# SCH_Led-Chaser_2025-10-31.net
KiCad netlist of a schematic drawn in EasyEDA
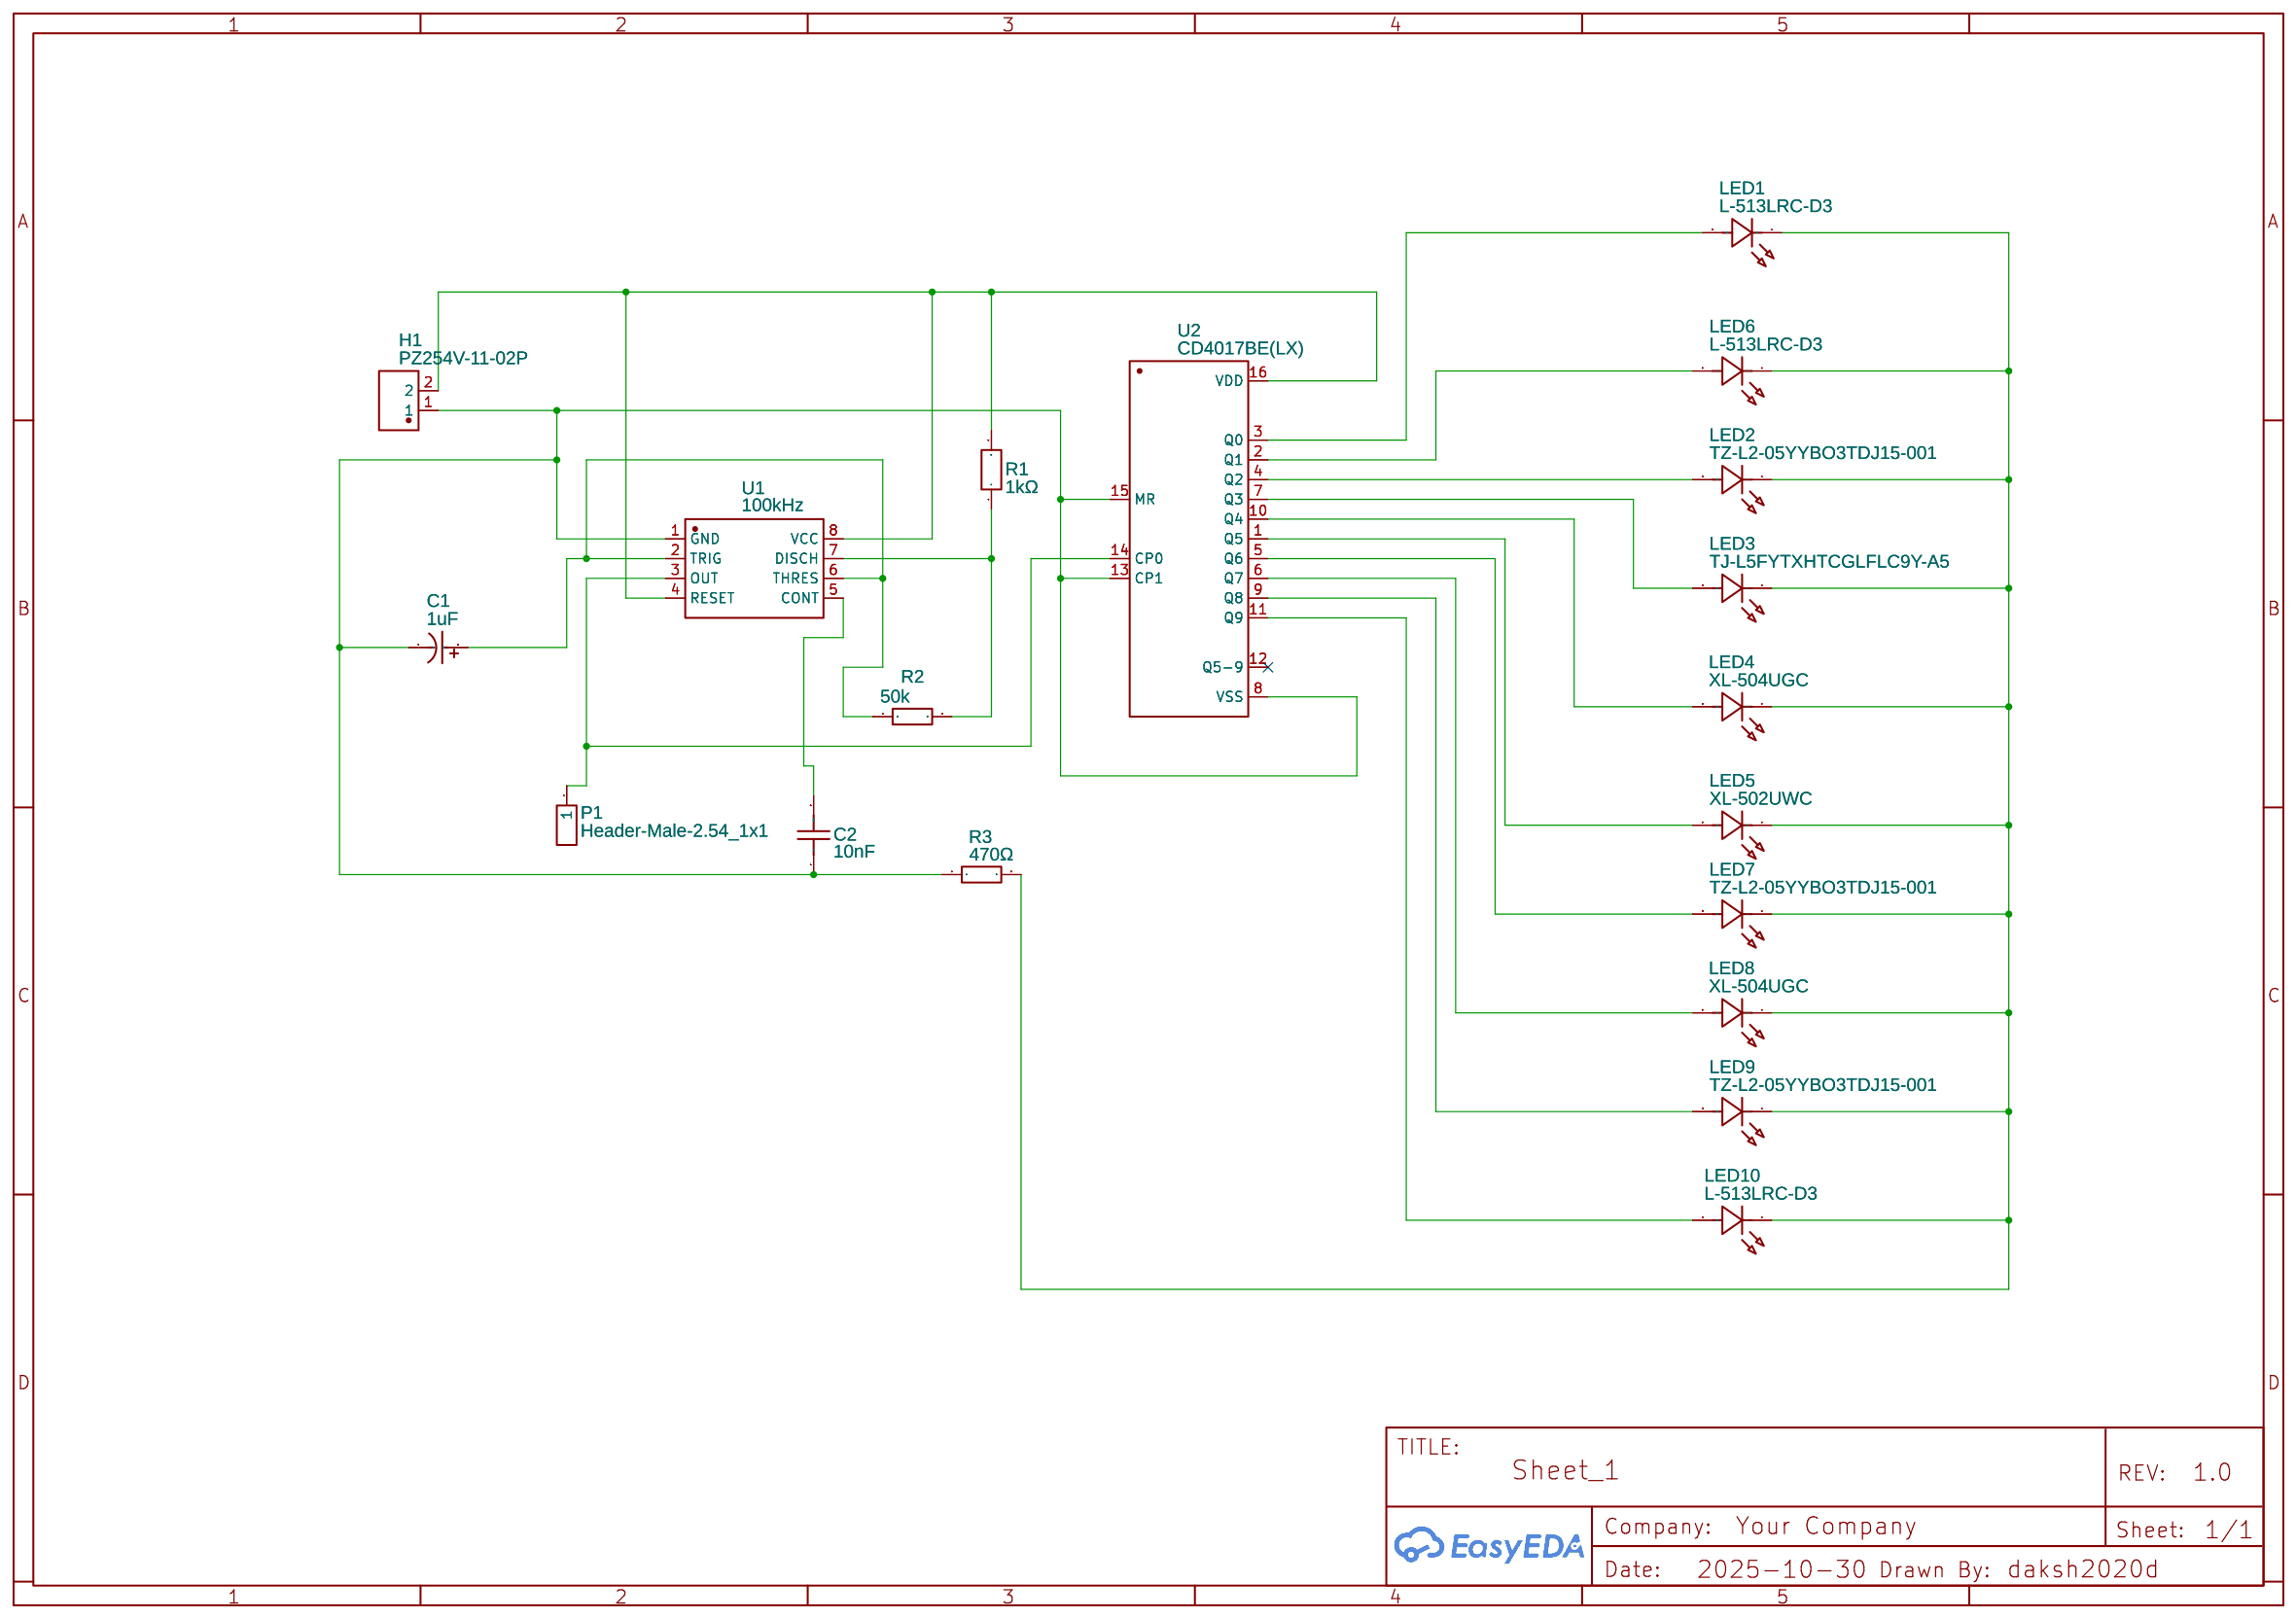
[diagram p0: schematic sheet]

(export (version "E")
  (design (tool "Eeschema 10.0.6"))
  (components
    (comp (ref "C1")
      (value "1uF")
      (fields (field (name "Manufacturer Part") "KF010M050C110A") (field (name "Manufacturer") "CapXon(丰宾)"))
      (libsource (lib "") (part "KF010M050C110A"))
    )
    (comp (ref "C2")
      (value "10nF")
      (fields (field (name "Manufacturer Part") "N09F1B103MN0B0S0N0") (field (name "Manufacturer") "STE(松田)"))
      (libsource (lib "") (part "N09F1B103MN0B0S0N0"))
    )
    (comp (ref "H1")
      (value "PZ254V-11-02P")
      (fields (field (name "Manufacturer") "XFCN(兴飞)"))
      (libsource (lib "") (part "PZ254V-11-02P"))
    )
    (comp (ref "LED1")
      (value "L-513LRC-D3")
      (fields (field (name "Manufacturer") "PARALIGHT(光鼎)"))
      (libsource (lib "") (part "L-513LRC-D3"))
    )
    (comp (ref "LED2")
      (value "TZ-L2-05YYBO3TDJ15-001")
      (fields (field (name "Manufacturer") "TUOZHAN(拓展光电)"))
      (libsource (lib "") (part "TZ-L2-05YYBO3TDJ15-001"))
    )
    (comp (ref "LED3")
      (value "TJ-L5FYTXHTCGLFLC9Y-A5")
      (fields (field (name "Manufacturer") "TOGIALED(统佳)"))
      (libsource (lib "") (part "TJ-L5FYTXHTCGLFLC9Y-A5"))
    )
    (comp (ref "LED4")
      (value "XL-504UGC")
      (fields (field (name "Manufacturer") "XINGLIGHT(成兴光)"))
      (libsource (lib "") (part "XL-504UGC"))
    )
    (comp (ref "LED5")
      (value "XL-502UWC")
      (fields (field (name "Manufacturer") "XINGLIGHT(成兴光)"))
      (libsource (lib "") (part "XL-502UWC"))
    )
    (comp (ref "LED6")
      (value "L-513LRC-D3")
      (fields (field (name "Manufacturer") "PARALIGHT(光鼎)"))
      (libsource (lib "") (part "L-513LRC-D3"))
    )
    (comp (ref "LED7")
      (value "TZ-L2-05YYBO3TDJ15-001")
      (fields (field (name "Manufacturer") "TUOZHAN(拓展光电)"))
      (libsource (lib "") (part "TZ-L2-05YYBO3TDJ15-001"))
    )
    (comp (ref "LED8")
      (value "XL-504UGC")
      (fields (field (name "Manufacturer") "XINGLIGHT(成兴光)"))
      (libsource (lib "") (part "XL-504UGC"))
    )
    (comp (ref "LED9")
      (value "TZ-L2-05YYBO3TDJ15-001")
      (fields (field (name "Manufacturer") "TUOZHAN(拓展光电)"))
      (libsource (lib "") (part "TZ-L2-05YYBO3TDJ15-001"))
    )
    (comp (ref "LED10")
      (value "L-513LRC-D3")
      (fields (field (name "Manufacturer") "PARALIGHT(光鼎)"))
      (libsource (lib "") (part "L-513LRC-D3"))
    )
    (comp (ref "P1")
      (value "Header-Male-2.54_1x1")
      (fields (field (name "Manufacturer Part") "2.54-1*1P针") (field (name "Manufacturer") "BOOMELE(博穆精密)"))
      (libsource (lib "") (part "Header-Male-2.54_1x1"))
    )
    (comp (ref "R1")
      (value "1kΩ")
      (fields (field (name "Manufacturer Part") "MF1/4W-1KΩ±1%T52") (field (name "Manufacturer") "华星机电"))
      (libsource (lib "") (part "MF1/4W-1KΩ±1%T52"))
    )
    (comp (ref "R2")
      (value "50k")
      (fields
        (field (name "Manufacturer Part") "MFR0W4F4700A50")
        (field (name "Manufacturer") "UNI-ROYAL(厚声)")
      )
      (libsource (lib "") (part "MFR0W4F4700A50"))
    )
    (comp (ref "R3")
      (value "470Ω")
      (fields
        (field (name "Manufacturer Part") "MFR0W4F4700A50")
        (field (name "Manufacturer") "UNI-ROYAL(厚声)")
      )
      (libsource (lib "") (part "MFR0W4F4700A50"))
    )
    (comp (ref "U1")
      (value "100kHz")
      (fields (field (name "Manufacturer Part") "NE555P") (field (name "Manufacturer") "TI(德州仪器)"))
      (libsource (lib "") (part "NE555P"))
    )
    (comp (ref "U2")
      (value "CD4017BE(LX)")
      (fields (field (name "Manufacturer") "LX(灵星芯微)"))
      (libsource (lib "") (part "CD4017BE(LX)"))
    )
  )
  (nets
    (net (code "1") (name "Net-(LED1-A)") (class "Default")
      (node (ref "LED1") (pin "2") (pinfunction "A_2") (pintype "unspecified"))
      (node (ref "U2") (pin "3") (pinfunction "Q0_3") (pintype "unspecified"))
    )
    (net (code "2") (name "Net-(LED1-K)") (class "Default")
      (node (ref "LED1") (pin "1") (pinfunction "K_1") (pintype "unspecified"))
      (node (ref "LED10") (pin "1") (pinfunction "K_1") (pintype "unspecified"))
      (node (ref "LED2") (pin "1") (pinfunction "-_1") (pintype "unspecified"))
      (node (ref "LED3") (pin "1") (pinfunction "-_1") (pintype "unspecified"))
      (node (ref "LED4") (pin "1") (pinfunction "K_1") (pintype "unspecified"))
      (node (ref "LED5") (pin "1") (pinfunction "K_1") (pintype "unspecified"))
      (node (ref "LED6") (pin "1") (pinfunction "K_1") (pintype "unspecified"))
      (node (ref "LED7") (pin "1") (pinfunction "-_1") (pintype "unspecified"))
      (node (ref "LED8") (pin "1") (pinfunction "K_1") (pintype "unspecified"))
      (node (ref "LED9") (pin "1") (pinfunction "-_1") (pintype "unspecified"))
      (node (ref "R3") (pin "2") (pinfunction "2_2") (pintype "input"))
    )
    (net (code "3") (name "Net-(LED2-+)") (class "Default")
      (node (ref "LED2") (pin "2") (pinfunction "+_2") (pintype "unspecified"))
      (node (ref "U2") (pin "4") (pinfunction "Q2_4") (pintype "unspecified"))
    )
    (net (code "4") (name "Net-(LED3-+)") (class "Default")
      (node (ref "LED3") (pin "2") (pinfunction "+_2") (pintype "unspecified"))
      (node (ref "U2") (pin "7") (pinfunction "Q3_7") (pintype "unspecified"))
    )
    (net (code "5") (name "Net-(LED4-A)") (class "Default")
      (node (ref "LED4") (pin "2") (pinfunction "A_2") (pintype "unspecified"))
      (node (ref "U2") (pin "10") (pinfunction "Q4_10") (pintype "unspecified"))
    )
    (net (code "6") (name "Net-(LED5-A)") (class "Default")
      (node (ref "LED5") (pin "2") (pinfunction "A_2") (pintype "unspecified"))
      (node (ref "U2") (pin "1") (pinfunction "Q5_1") (pintype "unspecified"))
    )
    (net (code "7") (name "Net-(LED6-A)") (class "Default")
      (node (ref "LED6") (pin "2") (pinfunction "A_2") (pintype "unspecified"))
      (node (ref "U2") (pin "2") (pinfunction "Q1_2") (pintype "unspecified"))
    )
    (net (code "8") (name "Net-(LED7-+)") (class "Default")
      (node (ref "LED7") (pin "2") (pinfunction "+_2") (pintype "unspecified"))
      (node (ref "U2") (pin "5") (pinfunction "Q6_5") (pintype "unspecified"))
    )
    (net (code "9") (name "Net-(LED8-A)") (class "Default")
      (node (ref "LED8") (pin "2") (pinfunction "A_2") (pintype "unspecified"))
      (node (ref "U2") (pin "6") (pinfunction "Q7_6") (pintype "unspecified"))
    )
    (net (code "10") (name "Net-(LED9-+)") (class "Default")
      (node (ref "LED9") (pin "2") (pinfunction "+_2") (pintype "unspecified"))
      (node (ref "U2") (pin "9") (pinfunction "Q8_9") (pintype "unspecified"))
    )
    (net (code "11") (name "Net-(LED10-A)") (class "Default")
      (node (ref "LED10") (pin "2") (pinfunction "A_2") (pintype "unspecified"))
      (node (ref "U2") (pin "11") (pinfunction "Q9_11") (pintype "unspecified"))
    )
    (net (code "12") (name "Net-(U1-CONT)") (class "Default")
      (node (ref "C2") (pin "2") (pinfunction "2_2") (pintype "unspecified"))
      (node (ref "U1") (pin "5") (pinfunction "CONT_5") (pintype "unspecified"))
    )
    (net (code "13") (name "Net-(U1-DISCH)") (class "Default")
      (node (ref "R1") (pin "1") (pinfunction "1_1") (pintype "unspecified"))
      (node (ref "R2") (pin "2") (pinfunction "2_2") (pintype "input"))
      (node (ref "U1") (pin "7") (pinfunction "DISCH_7") (pintype "unspecified"))
    )
    (net (code "14") (name "Net-(U1-GND)") (class "Default")
      (node (ref "C1") (pin "2") (pinfunction "2_2") (pintype "input"))
      (node (ref "C2") (pin "1") (pinfunction "1_1") (pintype "unspecified"))
      (node (ref "H1") (pin "1") (pinfunction "1_1") (pintype "unspecified"))
      (node (ref "R3") (pin "1") (pinfunction "1_1") (pintype "input"))
      (node (ref "U1") (pin "1") (pinfunction "GND_1") (pintype "unspecified"))
      (node (ref "U2") (pin "13") (pinfunction "CP1_13") (pintype "unspecified"))
      (node (ref "U2") (pin "15") (pinfunction "MR_15") (pintype "unspecified"))
      (node (ref "U2") (pin "8") (pinfunction "VSS_8") (pintype "unspecified"))
    )
    (net (code "15") (name "Net-(U1-OUT)") (class "Default")
      (node (ref "P1") (pin "1") (pinfunction "1_1") (pintype "input"))
      (node (ref "U1") (pin "3") (pinfunction "OUT_3") (pintype "unspecified"))
      (node (ref "U2") (pin "14") (pinfunction "CP0_14") (pintype "unspecified"))
    )
    (net (code "16") (name "Net-(U1-RESET)") (class "Default")
      (node (ref "H1") (pin "2") (pinfunction "2_2") (pintype "unspecified"))
      (node (ref "R1") (pin "2") (pinfunction "2_2") (pintype "unspecified"))
      (node (ref "U1") (pin "4") (pinfunction "RESET_4") (pintype "unspecified"))
      (node (ref "U1") (pin "8") (pinfunction "VCC_8") (pintype "unspecified"))
      (node (ref "U2") (pin "16") (pinfunction "VDD_16") (pintype "unspecified"))
    )
    (net (code "17") (name "Net-(U1-THRES)") (class "Default")
      (node (ref "C1") (pin "1") (pinfunction "1_1") (pintype "input"))
      (node (ref "R2") (pin "1") (pinfunction "1_1") (pintype "input"))
      (node (ref "U1") (pin "2") (pinfunction "TRIG_2") (pintype "unspecified"))
      (node (ref "U1") (pin "6") (pinfunction "THRES_6") (pintype "unspecified"))
    )
    (net (code "18") (name "unconnected-(U2-Q5-9-Pad12)") (class "Default")
      (node (ref "U2") (pin "12") (pinfunction "Q5-9_12") (pintype "unspecified+no_connect"))
    )
  )
)
